# LEDs.net
KiCad netlist of a schematic drawn in Altium Designer
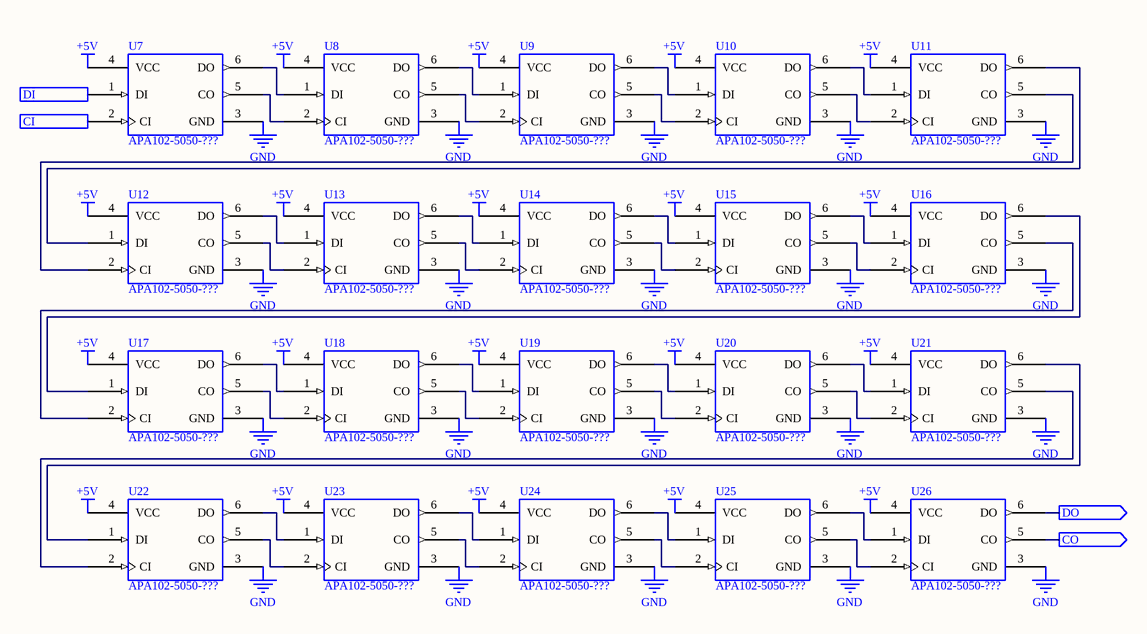
[diagram p0: LEDs.SchDoc]

(export (version "E")
  (design (tool "Eeschema 10.0.6"))
  (components
    (comp (ref "U7")
      (value "APA102-5050-???")
      (footprint "C2100EF9-5A1B-4012-AEAB-289AE8E97B6B")
      (description "IC SMD LED RGB DIGITAL APA102C-5050")
      (fields (field (name "PART NUMBER") "fe772892-1231-440c-ad15-efcb7032d7d7"))
      (libsource (lib "frmdblib") (part "B8F0CA09-B335-4B4D-8ECF-0D3C549F79C5"))
    )
    (comp (ref "U8")
      (value "APA102-5050-???")
      (footprint "C2100EF9-5A1B-4012-AEAB-289AE8E97B6B")
      (description "IC SMD LED RGB DIGITAL APA102C-5050")
      (fields (field (name "PART NUMBER") "fe772892-1231-440c-ad15-efcb7032d7d7"))
      (libsource (lib "frmdblib") (part "B8F0CA09-B335-4B4D-8ECF-0D3C549F79C5"))
    )
    (comp (ref "U9")
      (value "APA102-5050-???")
      (footprint "C2100EF9-5A1B-4012-AEAB-289AE8E97B6B")
      (description "IC SMD LED RGB DIGITAL APA102C-5050")
      (fields (field (name "PART NUMBER") "fe772892-1231-440c-ad15-efcb7032d7d7"))
      (libsource (lib "frmdblib") (part "B8F0CA09-B335-4B4D-8ECF-0D3C549F79C5"))
    )
    (comp (ref "U10")
      (value "APA102-5050-???")
      (footprint "C2100EF9-5A1B-4012-AEAB-289AE8E97B6B")
      (description "IC SMD LED RGB DIGITAL APA102C-5050")
      (fields (field (name "PART NUMBER") "fe772892-1231-440c-ad15-efcb7032d7d7"))
      (libsource (lib "frmdblib") (part "B8F0CA09-B335-4B4D-8ECF-0D3C549F79C5"))
    )
    (comp (ref "U11")
      (value "APA102-5050-???")
      (footprint "C2100EF9-5A1B-4012-AEAB-289AE8E97B6B")
      (description "IC SMD LED RGB DIGITAL APA102C-5050")
      (fields (field (name "PART NUMBER") "fe772892-1231-440c-ad15-efcb7032d7d7"))
      (libsource (lib "frmdblib") (part "B8F0CA09-B335-4B4D-8ECF-0D3C549F79C5"))
    )
    (comp (ref "U12")
      (value "APA102-5050-???")
      (footprint "C2100EF9-5A1B-4012-AEAB-289AE8E97B6B")
      (description "IC SMD LED RGB DIGITAL APA102C-5050")
      (fields (field (name "PART NUMBER") "fe772892-1231-440c-ad15-efcb7032d7d7"))
      (libsource (lib "frmdblib") (part "B8F0CA09-B335-4B4D-8ECF-0D3C549F79C5"))
    )
    (comp (ref "U13")
      (value "APA102-5050-???")
      (footprint "C2100EF9-5A1B-4012-AEAB-289AE8E97B6B")
      (description "IC SMD LED RGB DIGITAL APA102C-5050")
      (fields (field (name "PART NUMBER") "fe772892-1231-440c-ad15-efcb7032d7d7"))
      (libsource (lib "frmdblib") (part "B8F0CA09-B335-4B4D-8ECF-0D3C549F79C5"))
    )
    (comp (ref "U14")
      (value "APA102-5050-???")
      (footprint "C2100EF9-5A1B-4012-AEAB-289AE8E97B6B")
      (description "IC SMD LED RGB DIGITAL APA102C-5050")
      (fields (field (name "PART NUMBER") "fe772892-1231-440c-ad15-efcb7032d7d7"))
      (libsource (lib "frmdblib") (part "B8F0CA09-B335-4B4D-8ECF-0D3C549F79C5"))
    )
    (comp (ref "U15")
      (value "APA102-5050-???")
      (footprint "C2100EF9-5A1B-4012-AEAB-289AE8E97B6B")
      (description "IC SMD LED RGB DIGITAL APA102C-5050")
      (fields (field (name "PART NUMBER") "fe772892-1231-440c-ad15-efcb7032d7d7"))
      (libsource (lib "frmdblib") (part "B8F0CA09-B335-4B4D-8ECF-0D3C549F79C5"))
    )
    (comp (ref "U16")
      (value "APA102-5050-???")
      (footprint "C2100EF9-5A1B-4012-AEAB-289AE8E97B6B")
      (description "IC SMD LED RGB DIGITAL APA102C-5050")
      (fields (field (name "PART NUMBER") "fe772892-1231-440c-ad15-efcb7032d7d7"))
      (libsource (lib "frmdblib") (part "B8F0CA09-B335-4B4D-8ECF-0D3C549F79C5"))
    )
    (comp (ref "U17")
      (value "APA102-5050-???")
      (footprint "C2100EF9-5A1B-4012-AEAB-289AE8E97B6B")
      (description "IC SMD LED RGB DIGITAL APA102C-5050")
      (fields (field (name "PART NUMBER") "fe772892-1231-440c-ad15-efcb7032d7d7"))
      (libsource (lib "frmdblib") (part "B8F0CA09-B335-4B4D-8ECF-0D3C549F79C5"))
    )
    (comp (ref "U18")
      (value "APA102-5050-???")
      (footprint "C2100EF9-5A1B-4012-AEAB-289AE8E97B6B")
      (description "IC SMD LED RGB DIGITAL APA102C-5050")
      (fields (field (name "PART NUMBER") "fe772892-1231-440c-ad15-efcb7032d7d7"))
      (libsource (lib "frmdblib") (part "B8F0CA09-B335-4B4D-8ECF-0D3C549F79C5"))
    )
    (comp (ref "U19")
      (value "APA102-5050-???")
      (footprint "C2100EF9-5A1B-4012-AEAB-289AE8E97B6B")
      (description "IC SMD LED RGB DIGITAL APA102C-5050")
      (fields (field (name "PART NUMBER") "fe772892-1231-440c-ad15-efcb7032d7d7"))
      (libsource (lib "frmdblib") (part "B8F0CA09-B335-4B4D-8ECF-0D3C549F79C5"))
    )
    (comp (ref "U20")
      (value "APA102-5050-???")
      (footprint "C2100EF9-5A1B-4012-AEAB-289AE8E97B6B")
      (description "IC SMD LED RGB DIGITAL APA102C-5050")
      (fields (field (name "PART NUMBER") "fe772892-1231-440c-ad15-efcb7032d7d7"))
      (libsource (lib "frmdblib") (part "B8F0CA09-B335-4B4D-8ECF-0D3C549F79C5"))
    )
    (comp (ref "U21")
      (value "APA102-5050-???")
      (footprint "C2100EF9-5A1B-4012-AEAB-289AE8E97B6B")
      (description "IC SMD LED RGB DIGITAL APA102C-5050")
      (fields (field (name "PART NUMBER") "fe772892-1231-440c-ad15-efcb7032d7d7"))
      (libsource (lib "frmdblib") (part "B8F0CA09-B335-4B4D-8ECF-0D3C549F79C5"))
    )
    (comp (ref "U22")
      (value "APA102-5050-???")
      (footprint "C2100EF9-5A1B-4012-AEAB-289AE8E97B6B")
      (description "IC SMD LED RGB DIGITAL APA102C-5050")
      (fields (field (name "PART NUMBER") "fe772892-1231-440c-ad15-efcb7032d7d7"))
      (libsource (lib "frmdblib") (part "B8F0CA09-B335-4B4D-8ECF-0D3C549F79C5"))
    )
    (comp (ref "U23")
      (value "APA102-5050-???")
      (footprint "C2100EF9-5A1B-4012-AEAB-289AE8E97B6B")
      (description "IC SMD LED RGB DIGITAL APA102C-5050")
      (fields (field (name "PART NUMBER") "fe772892-1231-440c-ad15-efcb7032d7d7"))
      (libsource (lib "frmdblib") (part "B8F0CA09-B335-4B4D-8ECF-0D3C549F79C5"))
    )
    (comp (ref "U24")
      (value "APA102-5050-???")
      (footprint "C2100EF9-5A1B-4012-AEAB-289AE8E97B6B")
      (description "IC SMD LED RGB DIGITAL APA102C-5050")
      (fields (field (name "PART NUMBER") "fe772892-1231-440c-ad15-efcb7032d7d7"))
      (libsource (lib "frmdblib") (part "B8F0CA09-B335-4B4D-8ECF-0D3C549F79C5"))
    )
    (comp (ref "U25")
      (value "APA102-5050-???")
      (footprint "C2100EF9-5A1B-4012-AEAB-289AE8E97B6B")
      (description "IC SMD LED RGB DIGITAL APA102C-5050")
      (fields (field (name "PART NUMBER") "fe772892-1231-440c-ad15-efcb7032d7d7"))
      (libsource (lib "frmdblib") (part "B8F0CA09-B335-4B4D-8ECF-0D3C549F79C5"))
    )
    (comp (ref "U26")
      (value "APA102-5050-???")
      (footprint "C2100EF9-5A1B-4012-AEAB-289AE8E97B6B")
      (description "IC SMD LED RGB DIGITAL APA102C-5050")
      (fields (field (name "PART NUMBER") "fe772892-1231-440c-ad15-efcb7032d7d7"))
      (libsource (lib "frmdblib") (part "B8F0CA09-B335-4B4D-8ECF-0D3C549F79C5"))
    )
  )
  (nets
    (net (code "1") (name "+5V") (class "Default")
      (node (ref "U10") (pin "4") (pinfunction "VCC_4") (pintype "power_in"))
      (node (ref "U11") (pin "4") (pinfunction "VCC_4") (pintype "power_in"))
      (node (ref "U12") (pin "4") (pinfunction "VCC_4") (pintype "power_in"))
      (node (ref "U13") (pin "4") (pinfunction "VCC_4") (pintype "power_in"))
      (node (ref "U14") (pin "4") (pinfunction "VCC_4") (pintype "power_in"))
      (node (ref "U15") (pin "4") (pinfunction "VCC_4") (pintype "power_in"))
      (node (ref "U16") (pin "4") (pinfunction "VCC_4") (pintype "power_in"))
      (node (ref "U17") (pin "4") (pinfunction "VCC_4") (pintype "power_in"))
      (node (ref "U18") (pin "4") (pinfunction "VCC_4") (pintype "power_in"))
      (node (ref "U19") (pin "4") (pinfunction "VCC_4") (pintype "power_in"))
      (node (ref "U20") (pin "4") (pinfunction "VCC_4") (pintype "power_in"))
      (node (ref "U21") (pin "4") (pinfunction "VCC_4") (pintype "power_in"))
      (node (ref "U22") (pin "4") (pinfunction "VCC_4") (pintype "power_in"))
      (node (ref "U23") (pin "4") (pinfunction "VCC_4") (pintype "power_in"))
      (node (ref "U24") (pin "4") (pinfunction "VCC_4") (pintype "power_in"))
      (node (ref "U25") (pin "4") (pinfunction "VCC_4") (pintype "power_in"))
      (node (ref "U26") (pin "4") (pinfunction "VCC_4") (pintype "power_in"))
      (node (ref "U7") (pin "4") (pinfunction "VCC_4") (pintype "power_in"))
      (node (ref "U8") (pin "4") (pinfunction "VCC_4") (pintype "power_in"))
      (node (ref "U9") (pin "4") (pinfunction "VCC_4") (pintype "power_in"))
    )
    (net (code "2") (name "/CI") (class "Default")
      (node (ref "U7") (pin "2") (pinfunction "CI_2") (pintype "input"))
    )
    (net (code "3") (name "/CO") (class "Default")
      (node (ref "U26") (pin "5") (pinfunction "CO_5") (pintype "output"))
    )
    (net (code "4") (name "/DI") (class "Default")
      (node (ref "U7") (pin "1") (pinfunction "DI_1") (pintype "input"))
    )
    (net (code "5") (name "/DO") (class "Default")
      (node (ref "U26") (pin "6") (pinfunction "DO_6") (pintype "output"))
    )
    (net (code "6") (name "GND") (class "Default")
      (node (ref "U10") (pin "3") (pinfunction "GND_3") (pintype "power_in"))
      (node (ref "U11") (pin "3") (pinfunction "GND_3") (pintype "power_in"))
      (node (ref "U12") (pin "3") (pinfunction "GND_3") (pintype "power_in"))
      (node (ref "U13") (pin "3") (pinfunction "GND_3") (pintype "power_in"))
      (node (ref "U14") (pin "3") (pinfunction "GND_3") (pintype "power_in"))
      (node (ref "U15") (pin "3") (pinfunction "GND_3") (pintype "power_in"))
      (node (ref "U16") (pin "3") (pinfunction "GND_3") (pintype "power_in"))
      (node (ref "U17") (pin "3") (pinfunction "GND_3") (pintype "power_in"))
      (node (ref "U18") (pin "3") (pinfunction "GND_3") (pintype "power_in"))
      (node (ref "U19") (pin "3") (pinfunction "GND_3") (pintype "power_in"))
      (node (ref "U20") (pin "3") (pinfunction "GND_3") (pintype "power_in"))
      (node (ref "U21") (pin "3") (pinfunction "GND_3") (pintype "power_in"))
      (node (ref "U22") (pin "3") (pinfunction "GND_3") (pintype "power_in"))
      (node (ref "U23") (pin "3") (pinfunction "GND_3") (pintype "power_in"))
      (node (ref "U24") (pin "3") (pinfunction "GND_3") (pintype "power_in"))
      (node (ref "U25") (pin "3") (pinfunction "GND_3") (pintype "power_in"))
      (node (ref "U26") (pin "3") (pinfunction "GND_3") (pintype "power_in"))
      (node (ref "U7") (pin "3") (pinfunction "GND_3") (pintype "power_in"))
      (node (ref "U8") (pin "3") (pinfunction "GND_3") (pintype "power_in"))
      (node (ref "U9") (pin "3") (pinfunction "GND_3") (pintype "power_in"))
    )
    (net (code "7") (name "Net-(U7-CO)") (class "Default")
      (node (ref "U7") (pin "5") (pinfunction "CO_5") (pintype "output"))
      (node (ref "U8") (pin "2") (pinfunction "CI_2") (pintype "input"))
    )
    (net (code "8") (name "Net-(U7-DO)") (class "Default")
      (node (ref "U7") (pin "6") (pinfunction "DO_6") (pintype "output"))
      (node (ref "U8") (pin "1") (pinfunction "DI_1") (pintype "input"))
    )
    (net (code "9") (name "Net-(U8-CO)") (class "Default")
      (node (ref "U8") (pin "5") (pinfunction "CO_5") (pintype "output"))
      (node (ref "U9") (pin "2") (pinfunction "CI_2") (pintype "input"))
    )
    (net (code "10") (name "Net-(U8-DO)") (class "Default")
      (node (ref "U8") (pin "6") (pinfunction "DO_6") (pintype "output"))
      (node (ref "U9") (pin "1") (pinfunction "DI_1") (pintype "input"))
    )
    (net (code "11") (name "Net-(U10-CI)") (class "Default")
      (node (ref "U10") (pin "2") (pinfunction "CI_2") (pintype "input"))
      (node (ref "U9") (pin "5") (pinfunction "CO_5") (pintype "output"))
    )
    (net (code "12") (name "Net-(U10-CO)") (class "Default")
      (node (ref "U10") (pin "5") (pinfunction "CO_5") (pintype "output"))
      (node (ref "U11") (pin "2") (pinfunction "CI_2") (pintype "input"))
    )
    (net (code "13") (name "Net-(U10-DI)") (class "Default")
      (node (ref "U10") (pin "1") (pinfunction "DI_1") (pintype "input"))
      (node (ref "U9") (pin "6") (pinfunction "DO_6") (pintype "output"))
    )
    (net (code "14") (name "Net-(U10-DO)") (class "Default")
      (node (ref "U10") (pin "6") (pinfunction "DO_6") (pintype "output"))
      (node (ref "U11") (pin "1") (pinfunction "DI_1") (pintype "input"))
    )
    (net (code "15") (name "Net-(U11-CO)") (class "Default")
      (node (ref "U11") (pin "5") (pinfunction "CO_5") (pintype "output"))
      (node (ref "U12") (pin "2") (pinfunction "CI_2") (pintype "input"))
    )
    (net (code "16") (name "Net-(U11-DO)") (class "Default")
      (node (ref "U11") (pin "6") (pinfunction "DO_6") (pintype "output"))
      (node (ref "U12") (pin "1") (pinfunction "DI_1") (pintype "input"))
    )
    (net (code "17") (name "Net-(U12-CO)") (class "Default")
      (node (ref "U12") (pin "5") (pinfunction "CO_5") (pintype "output"))
      (node (ref "U13") (pin "2") (pinfunction "CI_2") (pintype "input"))
    )
    (net (code "18") (name "Net-(U12-DO)") (class "Default")
      (node (ref "U12") (pin "6") (pinfunction "DO_6") (pintype "output"))
      (node (ref "U13") (pin "1") (pinfunction "DI_1") (pintype "input"))
    )
    (net (code "19") (name "Net-(U13-CO)") (class "Default")
      (node (ref "U13") (pin "5") (pinfunction "CO_5") (pintype "output"))
      (node (ref "U14") (pin "2") (pinfunction "CI_2") (pintype "input"))
    )
    (net (code "20") (name "Net-(U13-DO)") (class "Default")
      (node (ref "U13") (pin "6") (pinfunction "DO_6") (pintype "output"))
      (node (ref "U14") (pin "1") (pinfunction "DI_1") (pintype "input"))
    )
    (net (code "21") (name "Net-(U14-CO)") (class "Default")
      (node (ref "U14") (pin "5") (pinfunction "CO_5") (pintype "output"))
      (node (ref "U15") (pin "2") (pinfunction "CI_2") (pintype "input"))
    )
    (net (code "22") (name "Net-(U14-DO)") (class "Default")
      (node (ref "U14") (pin "6") (pinfunction "DO_6") (pintype "output"))
      (node (ref "U15") (pin "1") (pinfunction "DI_1") (pintype "input"))
    )
    (net (code "23") (name "Net-(U15-CO)") (class "Default")
      (node (ref "U15") (pin "5") (pinfunction "CO_5") (pintype "output"))
      (node (ref "U16") (pin "2") (pinfunction "CI_2") (pintype "input"))
    )
    (net (code "24") (name "Net-(U15-DO)") (class "Default")
      (node (ref "U15") (pin "6") (pinfunction "DO_6") (pintype "output"))
      (node (ref "U16") (pin "1") (pinfunction "DI_1") (pintype "input"))
    )
    (net (code "25") (name "Net-(U16-CO)") (class "Default")
      (node (ref "U16") (pin "5") (pinfunction "CO_5") (pintype "output"))
      (node (ref "U17") (pin "2") (pinfunction "CI_2") (pintype "input"))
    )
    (net (code "26") (name "Net-(U16-DO)") (class "Default")
      (node (ref "U16") (pin "6") (pinfunction "DO_6") (pintype "output"))
      (node (ref "U17") (pin "1") (pinfunction "DI_1") (pintype "input"))
    )
    (net (code "27") (name "Net-(U17-CO)") (class "Default")
      (node (ref "U17") (pin "5") (pinfunction "CO_5") (pintype "output"))
      (node (ref "U18") (pin "2") (pinfunction "CI_2") (pintype "input"))
    )
    (net (code "28") (name "Net-(U17-DO)") (class "Default")
      (node (ref "U17") (pin "6") (pinfunction "DO_6") (pintype "output"))
      (node (ref "U18") (pin "1") (pinfunction "DI_1") (pintype "input"))
    )
    (net (code "29") (name "Net-(U18-CO)") (class "Default")
      (node (ref "U18") (pin "5") (pinfunction "CO_5") (pintype "output"))
      (node (ref "U19") (pin "2") (pinfunction "CI_2") (pintype "input"))
    )
    (net (code "30") (name "Net-(U18-DO)") (class "Default")
      (node (ref "U18") (pin "6") (pinfunction "DO_6") (pintype "output"))
      (node (ref "U19") (pin "1") (pinfunction "DI_1") (pintype "input"))
    )
    (net (code "31") (name "Net-(U19-CO)") (class "Default")
      (node (ref "U19") (pin "5") (pinfunction "CO_5") (pintype "output"))
      (node (ref "U20") (pin "2") (pinfunction "CI_2") (pintype "input"))
    )
    (net (code "32") (name "Net-(U19-DO)") (class "Default")
      (node (ref "U19") (pin "6") (pinfunction "DO_6") (pintype "output"))
      (node (ref "U20") (pin "1") (pinfunction "DI_1") (pintype "input"))
    )
    (net (code "33") (name "Net-(U20-CO)") (class "Default")
      (node (ref "U20") (pin "5") (pinfunction "CO_5") (pintype "output"))
      (node (ref "U21") (pin "2") (pinfunction "CI_2") (pintype "input"))
    )
    (net (code "34") (name "Net-(U20-DO)") (class "Default")
      (node (ref "U20") (pin "6") (pinfunction "DO_6") (pintype "output"))
      (node (ref "U21") (pin "1") (pinfunction "DI_1") (pintype "input"))
    )
    (net (code "35") (name "Net-(U21-CO)") (class "Default")
      (node (ref "U21") (pin "5") (pinfunction "CO_5") (pintype "output"))
      (node (ref "U22") (pin "2") (pinfunction "CI_2") (pintype "input"))
    )
    (net (code "36") (name "Net-(U21-DO)") (class "Default")
      (node (ref "U21") (pin "6") (pinfunction "DO_6") (pintype "output"))
      (node (ref "U22") (pin "1") (pinfunction "DI_1") (pintype "input"))
    )
    (net (code "37") (name "Net-(U22-CO)") (class "Default")
      (node (ref "U22") (pin "5") (pinfunction "CO_5") (pintype "output"))
      (node (ref "U23") (pin "2") (pinfunction "CI_2") (pintype "input"))
    )
    (net (code "38") (name "Net-(U22-DO)") (class "Default")
      (node (ref "U22") (pin "6") (pinfunction "DO_6") (pintype "output"))
      (node (ref "U23") (pin "1") (pinfunction "DI_1") (pintype "input"))
    )
    (net (code "39") (name "Net-(U23-CO)") (class "Default")
      (node (ref "U23") (pin "5") (pinfunction "CO_5") (pintype "output"))
      (node (ref "U24") (pin "2") (pinfunction "CI_2") (pintype "input"))
    )
    (net (code "40") (name "Net-(U23-DO)") (class "Default")
      (node (ref "U23") (pin "6") (pinfunction "DO_6") (pintype "output"))
      (node (ref "U24") (pin "1") (pinfunction "DI_1") (pintype "input"))
    )
    (net (code "41") (name "Net-(U24-CO)") (class "Default")
      (node (ref "U24") (pin "5") (pinfunction "CO_5") (pintype "output"))
      (node (ref "U25") (pin "2") (pinfunction "CI_2") (pintype "input"))
    )
    (net (code "42") (name "Net-(U24-DO)") (class "Default")
      (node (ref "U24") (pin "6") (pinfunction "DO_6") (pintype "output"))
      (node (ref "U25") (pin "1") (pinfunction "DI_1") (pintype "input"))
    )
    (net (code "43") (name "Net-(U25-CO)") (class "Default")
      (node (ref "U25") (pin "5") (pinfunction "CO_5") (pintype "output"))
      (node (ref "U26") (pin "2") (pinfunction "CI_2") (pintype "input"))
    )
    (net (code "44") (name "Net-(U25-DO)") (class "Default")
      (node (ref "U25") (pin "6") (pinfunction "DO_6") (pintype "output"))
      (node (ref "U26") (pin "1") (pinfunction "DI_1") (pintype "input"))
    )
  )
)
